# Arduino_Shield.net
KiCad netlist of a schematic drawn in EAGLE
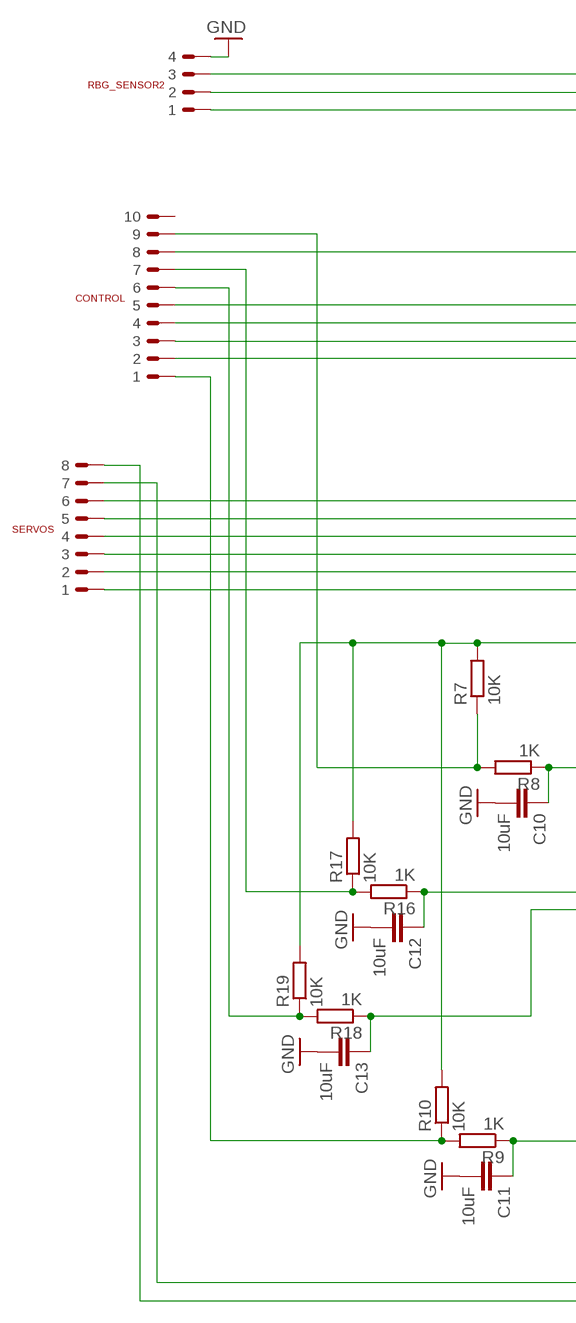
[diagram p0: schematic, sheet 1, part 1 of 2]
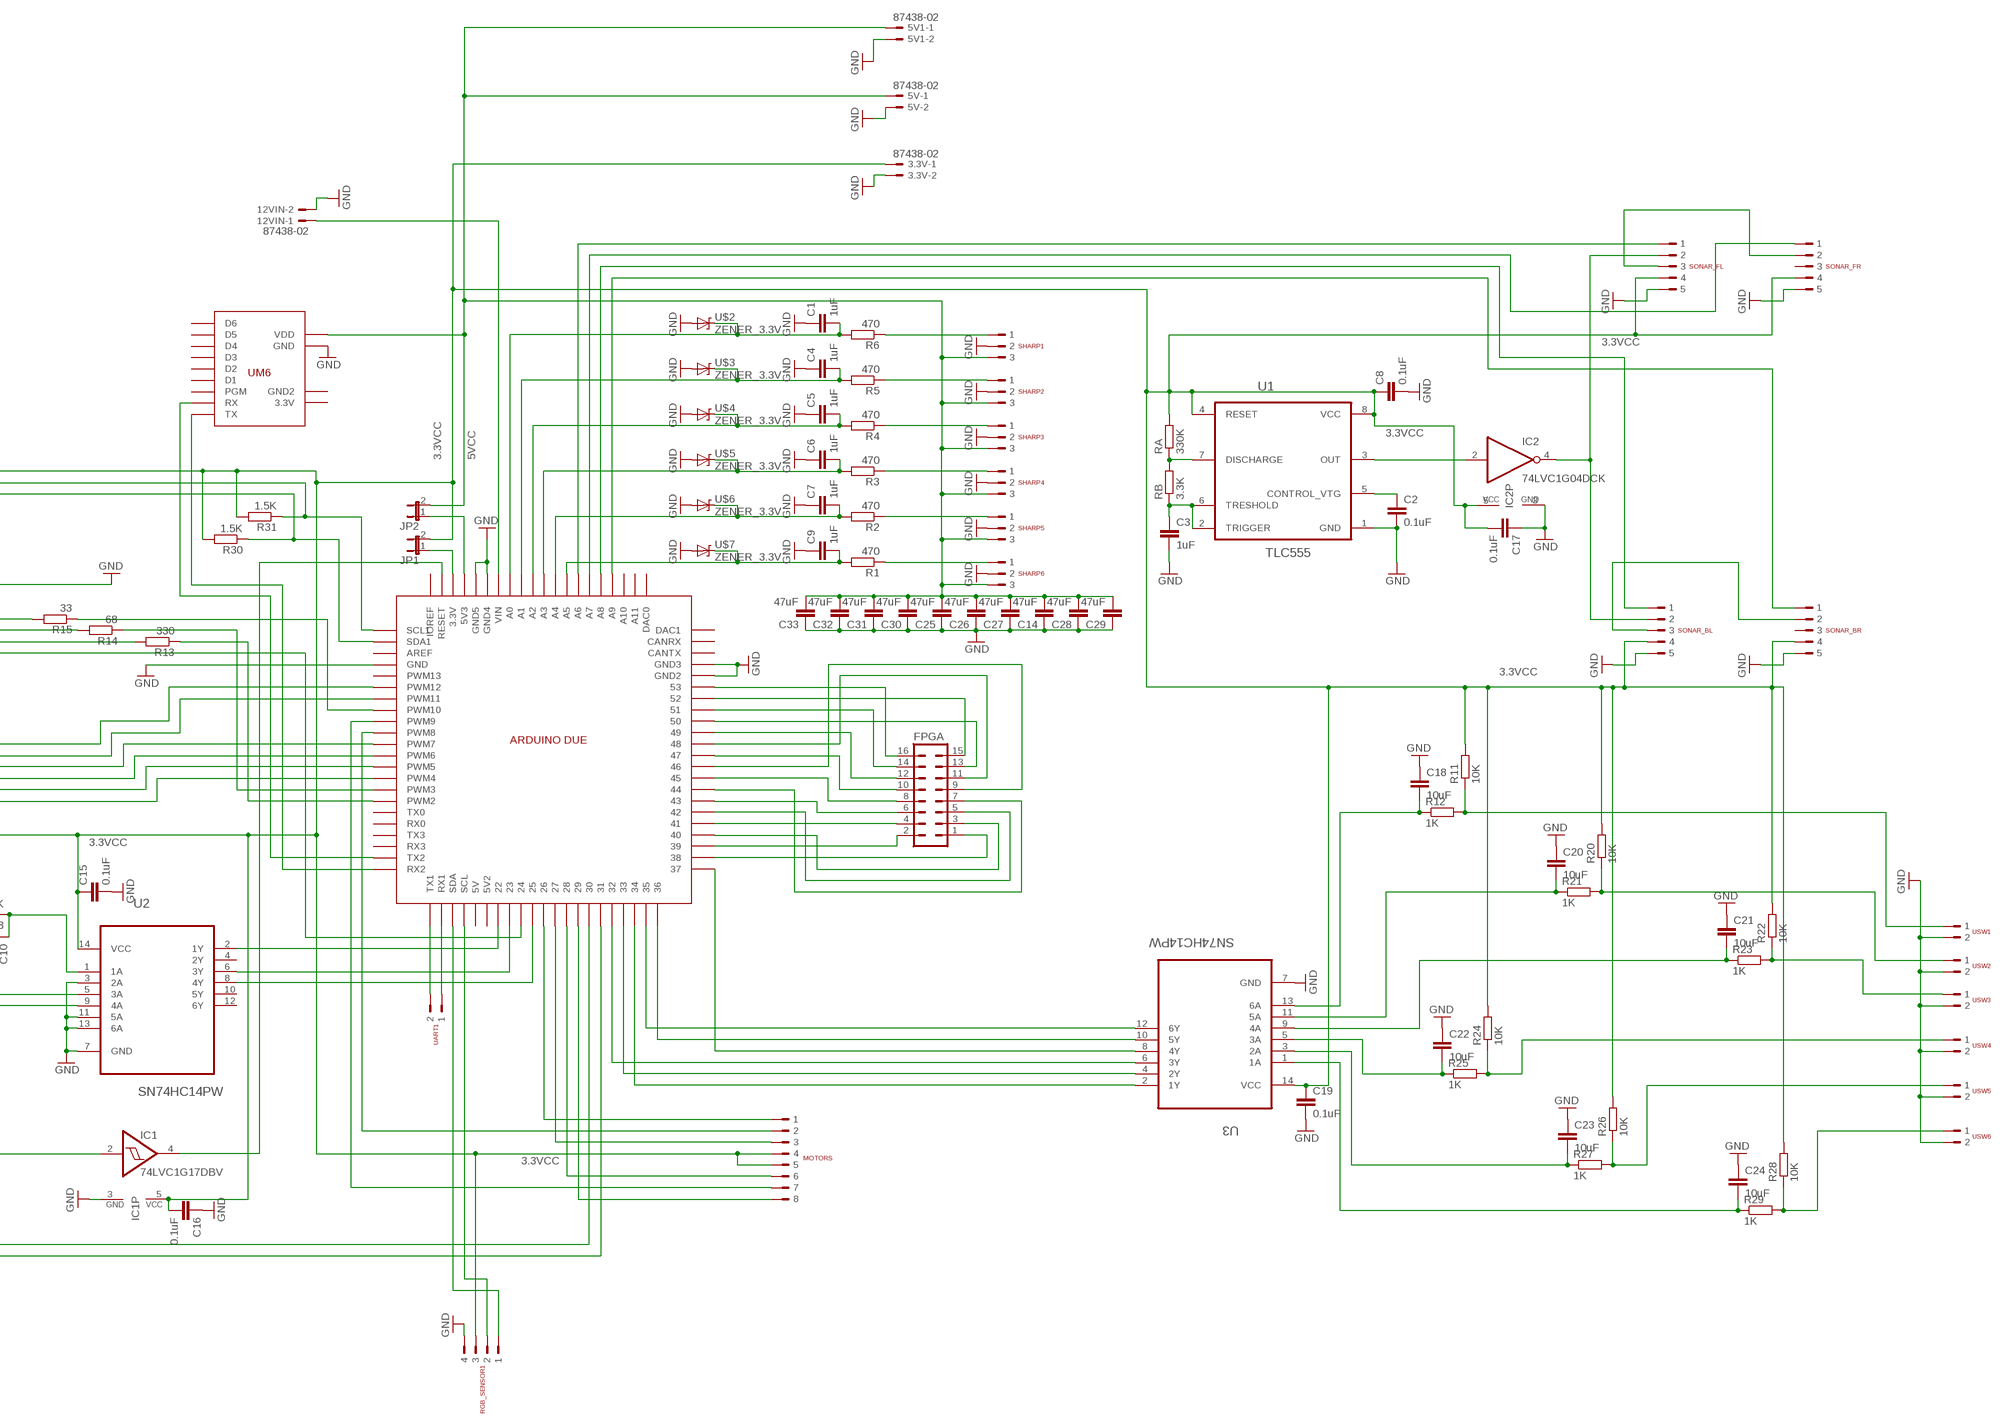
[diagram p1: schematic, sheet 1, part 2 of 2]

(export (version "E")
  (design (tool "Eeschema 10.0.6"))
  (components
    (comp (ref "3.3V")
      (value "87438-02")
      (footprint "eagle-import:87438-02")
      (libsource (lib "eagle-import") (part "87438-02"))
    )
    (comp (ref "5V")
      (value "87438-02")
      (footprint "eagle-import:87438-02")
      (libsource (lib "eagle-import") (part "87438-02"))
    )
    (comp (ref "5V1")
      (value "87438-02")
      (footprint "eagle-import:87438-02")
      (libsource (lib "eagle-import") (part "87438-02"))
    )
    (comp (ref "12VIN")
      (value "87438-02")
      (footprint "eagle-import:87438-02")
      (libsource (lib "eagle-import") (part "87438-02"))
    )
    (comp (ref "C1")
      (value "1uF")
      (footprint "eagle-import:C0603")
      (libsource (lib "eagle-import") (part "C-EUC0603"))
    )
    (comp (ref "C2")
      (value "0.1uF")
      (footprint "eagle-import:C0603")
      (libsource (lib "eagle-import") (part "C-EUC0603"))
    )
    (comp (ref "C3")
      (value "1uF")
      (footprint "eagle-import:C0603")
      (libsource (lib "eagle-import") (part "C-EUC0603"))
    )
    (comp (ref "C4")
      (value "1uF")
      (footprint "eagle-import:C0603")
      (libsource (lib "eagle-import") (part "C-EUC0603"))
    )
    (comp (ref "C5")
      (value "1uF")
      (footprint "eagle-import:C0603")
      (libsource (lib "eagle-import") (part "C-EUC0603"))
    )
    (comp (ref "C6")
      (value "1uF")
      (footprint "eagle-import:C0603")
      (libsource (lib "eagle-import") (part "C-EUC0603"))
    )
    (comp (ref "C7")
      (value "1uF")
      (footprint "eagle-import:C0603")
      (libsource (lib "eagle-import") (part "C-EUC0603"))
    )
    (comp (ref "C8")
      (value "0.1uF")
      (footprint "eagle-import:C0603")
      (libsource (lib "eagle-import") (part "C-EUC0603"))
    )
    (comp (ref "C9")
      (value "1uF")
      (footprint "eagle-import:C0603")
      (libsource (lib "eagle-import") (part "C-EUC0603"))
    )
    (comp (ref "C10")
      (value "10uF")
      (footprint "eagle-import:C0603")
      (libsource (lib "eagle-import") (part "C-EUC0603"))
    )
    (comp (ref "C11")
      (value "10uF")
      (footprint "eagle-import:C0603")
      (libsource (lib "eagle-import") (part "C-EUC0603"))
    )
    (comp (ref "C12")
      (value "10uF")
      (footprint "eagle-import:C0603")
      (libsource (lib "eagle-import") (part "C-EUC0603"))
    )
    (comp (ref "C13")
      (value "10uF")
      (footprint "eagle-import:C0603")
      (libsource (lib "eagle-import") (part "C-EUC0603"))
    )
    (comp (ref "C14")
      (value "47uF")
      (footprint "eagle-import:C1206")
      (libsource (lib "eagle-import") (part "C-EUC1206"))
    )
    (comp (ref "C15")
      (value "0.1uF")
      (footprint "eagle-import:C0603")
      (libsource (lib "eagle-import") (part "C-EUC0603"))
    )
    (comp (ref "C16")
      (value "0.1uF")
      (footprint "eagle-import:C0603")
      (libsource (lib "eagle-import") (part "C-EUC0603"))
    )
    (comp (ref "C17")
      (value "0.1uF")
      (footprint "eagle-import:C0603")
      (libsource (lib "eagle-import") (part "C-EUC0603"))
    )
    (comp (ref "C18")
      (value "10uF")
      (footprint "eagle-import:C0603")
      (libsource (lib "eagle-import") (part "C-EUC0603"))
    )
    (comp (ref "C19")
      (value "0.1uF")
      (footprint "eagle-import:C0603")
      (libsource (lib "eagle-import") (part "C-EUC0603"))
    )
    (comp (ref "C20")
      (value "10uF")
      (footprint "eagle-import:C0603")
      (libsource (lib "eagle-import") (part "C-EUC0603"))
    )
    (comp (ref "C21")
      (value "10uF")
      (footprint "eagle-import:C0603")
      (libsource (lib "eagle-import") (part "C-EUC0603"))
    )
    (comp (ref "C22")
      (value "10uF")
      (footprint "eagle-import:C0603")
      (libsource (lib "eagle-import") (part "C-EUC0603"))
    )
    (comp (ref "C23")
      (value "10uF")
      (footprint "eagle-import:C0603")
      (libsource (lib "eagle-import") (part "C-EUC0603"))
    )
    (comp (ref "C24")
      (value "10uF")
      (footprint "eagle-import:C0603")
      (libsource (lib "eagle-import") (part "C-EUC0603"))
    )
    (comp (ref "C25")
      (value "47uF")
      (footprint "eagle-import:C1206")
      (libsource (lib "eagle-import") (part "C-EUC1206"))
    )
    (comp (ref "C26")
      (value "47uF")
      (footprint "eagle-import:C1206")
      (libsource (lib "eagle-import") (part "C-EUC1206"))
    )
    (comp (ref "C27")
      (value "47uF")
      (footprint "eagle-import:C1206")
      (libsource (lib "eagle-import") (part "C-EUC1206"))
    )
    (comp (ref "C28")
      (value "47uF")
      (footprint "eagle-import:C1206")
      (libsource (lib "eagle-import") (part "C-EUC1206"))
    )
    (comp (ref "C29")
      (value "47uF")
      (footprint "eagle-import:C1206")
      (libsource (lib "eagle-import") (part "C-EUC1206"))
    )
    (comp (ref "C30")
      (value "47uF")
      (footprint "eagle-import:C1206")
      (libsource (lib "eagle-import") (part "C-EUC1206"))
    )
    (comp (ref "C31")
      (value "47uF")
      (footprint "eagle-import:C1206")
      (libsource (lib "eagle-import") (part "C-EUC1206"))
    )
    (comp (ref "C32")
      (value "47uF")
      (footprint "eagle-import:C1206")
      (libsource (lib "eagle-import") (part "C-EUC1206"))
    )
    (comp (ref "C33")
      (value "47uF")
      (footprint "eagle-import:C1206")
      (libsource (lib "eagle-import") (part "C-EUC1206"))
    )
    (comp (ref "CONTROL")
      (value "87437-1043")
      (footprint "eagle-import:87437-1043")
      (libsource (lib "eagle-import") (part "87437-1043"))
    )
    (comp (ref "FPGA")
      (value "ML16")
      (footprint "eagle-import:ML16")
      (libsource (lib "eagle-import") (part "ML16"))
    )
    (comp (ref "IC1")
      (value "74LVC1G17DBV")
      (footprint "eagle-import:SOT23-5")
      (libsource (lib "eagle-import") (part "741G17DBVLVC"))
    )
    (comp (ref "IC2")
      (value "74LVC1G04DCK")
      (footprint "eagle-import:SC70-5")
      (libsource (lib "eagle-import") (part "741G04DCKLVC"))
    )
    (comp (ref "JP1")
      (value "JP1E")
      (footprint "eagle-import:JP1")
      (libsource (lib "eagle-import") (part "JP1E"))
    )
    (comp (ref "JP2")
      (value "JP1E")
      (footprint "eagle-import:JP1")
      (libsource (lib "eagle-import") (part "JP1E"))
    )
    (comp (ref "MOTORS")
      (value "87437-0843")
      (footprint "eagle-import:87437-0843")
      (libsource (lib "eagle-import") (part "87437-0843"))
    )
    (comp (ref "R1")
      (value "470")
      (footprint "eagle-import:R0603")
      (libsource (lib "eagle-import") (part "R-EU_R0603"))
    )
    (comp (ref "R2")
      (value "470")
      (footprint "eagle-import:R0603")
      (libsource (lib "eagle-import") (part "R-EU_R0603"))
    )
    (comp (ref "R3")
      (value "470")
      (footprint "eagle-import:R0603")
      (libsource (lib "eagle-import") (part "R-EU_R0603"))
    )
    (comp (ref "R4")
      (value "470")
      (footprint "eagle-import:R0603")
      (libsource (lib "eagle-import") (part "R-EU_R0603"))
    )
    (comp (ref "R5")
      (value "470")
      (footprint "eagle-import:R0603")
      (libsource (lib "eagle-import") (part "R-EU_R0603"))
    )
    (comp (ref "R6")
      (value "470")
      (footprint "eagle-import:R0603")
      (libsource (lib "eagle-import") (part "R-EU_R0603"))
    )
    (comp (ref "R7")
      (value "10K")
      (footprint "eagle-import:R0603")
      (libsource (lib "eagle-import") (part "R-EU_R0603"))
    )
    (comp (ref "R8")
      (value "1K")
      (footprint "eagle-import:R0603")
      (libsource (lib "eagle-import") (part "R-EU_R0603"))
    )
    (comp (ref "R9")
      (value "1K")
      (footprint "eagle-import:R0603")
      (libsource (lib "eagle-import") (part "R-EU_R0603"))
    )
    (comp (ref "R10")
      (value "10K")
      (footprint "eagle-import:R0603")
      (libsource (lib "eagle-import") (part "R-EU_R0603"))
    )
    (comp (ref "R11")
      (value "10K")
      (footprint "eagle-import:R0603")
      (libsource (lib "eagle-import") (part "R-EU_R0603"))
    )
    (comp (ref "R12")
      (value "1K")
      (footprint "eagle-import:R0603")
      (libsource (lib "eagle-import") (part "R-EU_R0603"))
    )
    (comp (ref "R13")
      (value "330")
      (footprint "eagle-import:R0603")
      (libsource (lib "eagle-import") (part "R-EU_R0603"))
    )
    (comp (ref "R14")
      (value "68")
      (footprint "eagle-import:R0603")
      (libsource (lib "eagle-import") (part "R-EU_R0603"))
    )
    (comp (ref "R15")
      (value "33")
      (footprint "eagle-import:R0603")
      (libsource (lib "eagle-import") (part "R-EU_R0603"))
    )
    (comp (ref "R16")
      (value "1K")
      (footprint "eagle-import:R0603")
      (libsource (lib "eagle-import") (part "R-EU_R0603"))
    )
    (comp (ref "R17")
      (value "10K")
      (footprint "eagle-import:R0603")
      (libsource (lib "eagle-import") (part "R-EU_R0603"))
    )
    (comp (ref "R18")
      (value "1K")
      (footprint "eagle-import:R0603")
      (libsource (lib "eagle-import") (part "R-EU_R0603"))
    )
    (comp (ref "R19")
      (value "10K")
      (footprint "eagle-import:R0603")
      (libsource (lib "eagle-import") (part "R-EU_R0603"))
    )
    (comp (ref "R20")
      (value "10K")
      (footprint "eagle-import:R0603")
      (libsource (lib "eagle-import") (part "R-EU_R0603"))
    )
    (comp (ref "R21")
      (value "1K")
      (footprint "eagle-import:R0603")
      (libsource (lib "eagle-import") (part "R-EU_R0603"))
    )
    (comp (ref "R22")
      (value "10K")
      (footprint "eagle-import:R0603")
      (libsource (lib "eagle-import") (part "R-EU_R0603"))
    )
    (comp (ref "R23")
      (value "1K")
      (footprint "eagle-import:R0603")
      (libsource (lib "eagle-import") (part "R-EU_R0603"))
    )
    (comp (ref "R24")
      (value "10K")
      (footprint "eagle-import:R0603")
      (libsource (lib "eagle-import") (part "R-EU_R0603"))
    )
    (comp (ref "R25")
      (value "1K")
      (footprint "eagle-import:R0603")
      (libsource (lib "eagle-import") (part "R-EU_R0603"))
    )
    (comp (ref "R26")
      (value "10K")
      (footprint "eagle-import:R0603")
      (libsource (lib "eagle-import") (part "R-EU_R0603"))
    )
    (comp (ref "R27")
      (value "1K")
      (footprint "eagle-import:R0603")
      (libsource (lib "eagle-import") (part "R-EU_R0603"))
    )
    (comp (ref "R28")
      (value "10K")
      (footprint "eagle-import:R0603")
      (libsource (lib "eagle-import") (part "R-EU_R0603"))
    )
    (comp (ref "R29")
      (value "1K")
      (footprint "eagle-import:R0603")
      (libsource (lib "eagle-import") (part "R-EU_R0603"))
    )
    (comp (ref "R30")
      (value "1.5K")
      (footprint "eagle-import:R0603")
      (libsource (lib "eagle-import") (part "R-EU_R0603"))
    )
    (comp (ref "R31")
      (value "1.5K")
      (footprint "eagle-import:R0603")
      (libsource (lib "eagle-import") (part "R-EU_R0603"))
    )
    (comp (ref "RA")
      (value "330K")
      (footprint "eagle-import:R0603")
      (libsource (lib "eagle-import") (part "R-EU_R0603"))
    )
    (comp (ref "RB")
      (value "3.3K")
      (footprint "eagle-import:R0603")
      (libsource (lib "eagle-import") (part "R-EU_R0603"))
    )
    (comp (ref "RBG_SENSOR2")
      (value "87437-0443")
      (footprint "eagle-import:87437-0443")
      (libsource (lib "eagle-import") (part "87437-0443"))
    )
    (comp (ref "RGB_SENSOR1")
      (value "87437-0443")
      (footprint "eagle-import:87437-0443")
      (libsource (lib "eagle-import") (part "87437-0443"))
    )
    (comp (ref "SERVOS")
      (value "87437-0843")
      (footprint "eagle-import:87437-0843")
      (libsource (lib "eagle-import") (part "87437-0843"))
    )
    (comp (ref "SHARP1")
      (value "87437-0343")
      (footprint "eagle-import:87437-0343")
      (libsource (lib "eagle-import") (part "87437-0343"))
    )
    (comp (ref "SHARP2")
      (value "87437-0343")
      (footprint "eagle-import:87437-0343")
      (libsource (lib "eagle-import") (part "87437-0343"))
    )
    (comp (ref "SHARP3")
      (value "87437-0343")
      (footprint "eagle-import:87437-0343")
      (libsource (lib "eagle-import") (part "87437-0343"))
    )
    (comp (ref "SHARP4")
      (value "87437-0343")
      (footprint "eagle-import:87437-0343")
      (libsource (lib "eagle-import") (part "87437-0343"))
    )
    (comp (ref "SHARP5")
      (value "87437-0343")
      (footprint "eagle-import:87437-0343")
      (libsource (lib "eagle-import") (part "87437-0343"))
    )
    (comp (ref "SHARP6")
      (value "87437-0343")
      (footprint "eagle-import:87437-0343")
      (libsource (lib "eagle-import") (part "87437-0343"))
    )
    (comp (ref "SONAR_BL")
      (value "87437-0543")
      (footprint "eagle-import:87437-0543")
      (libsource (lib "eagle-import") (part "87437-0543"))
    )
    (comp (ref "SONAR_BR")
      (value "87437-0543")
      (footprint "eagle-import:87437-0543")
      (libsource (lib "eagle-import") (part "87437-0543"))
    )
    (comp (ref "SONAR_FL")
      (value "87437-0543")
      (footprint "eagle-import:87437-0543")
      (libsource (lib "eagle-import") (part "87437-0543"))
    )
    (comp (ref "SONAR_FR")
      (value "87437-0543")
      (footprint "eagle-import:87437-0543")
      (libsource (lib "eagle-import") (part "87437-0543"))
    )
    (comp (ref "U$1")
      (value "ARDUINO-DUE")
      (footprint "eagle-import:ARDUINO-DUE")
      (libsource (lib "eagle-import") (part "ARDUINO-DUE"))
    )
    (comp (ref "U$2")
      (value "ZENER_3.3V")
      (footprint "eagle-import:SOD-323")
      (libsource (lib "eagle-import") (part "DIODE-ZENER-BZT52"))
    )
    (comp (ref "U$3")
      (value "ZENER_3.3V")
      (footprint "eagle-import:SOD-323")
      (libsource (lib "eagle-import") (part "DIODE-ZENER-BZT52"))
    )
    (comp (ref "U$4")
      (value "ZENER_3.3V")
      (footprint "eagle-import:SOD-323")
      (libsource (lib "eagle-import") (part "DIODE-ZENER-BZT52"))
    )
    (comp (ref "U$5")
      (value "ZENER_3.3V")
      (footprint "eagle-import:SOD-323")
      (libsource (lib "eagle-import") (part "DIODE-ZENER-BZT52"))
    )
    (comp (ref "U$6")
      (value "ZENER_3.3V")
      (footprint "eagle-import:SOD-323")
      (libsource (lib "eagle-import") (part "DIODE-ZENER-BZT52"))
    )
    (comp (ref "U$7")
      (value "ZENER_3.3V")
      (footprint "eagle-import:SOD-323")
      (libsource (lib "eagle-import") (part "DIODE-ZENER-BZT52"))
    )
    (comp (ref "U1")
      (value "TLC555")
      (footprint "eagle-import:SOIC127P600X175-8N")
      (fields (field (name "MPN") "LM555CM"))
      (libsource (lib "eagle-import") (part "LM555CM"))
    )
    (comp (ref "U2")
      (value "SN74HC14PW")
      (footprint "eagle-import:SOP65P640X120-14N")
      (libsource (lib "eagle-import") (part "SN74HC14PW"))
    )
    (comp (ref "U3")
      (value "SN74HC14PW")
      (footprint "eagle-import:SOP65P640X120-14N")
      (libsource (lib "eagle-import") (part "SN74HC14PW"))
    )
    (comp (ref "UART1")
      (value "87437-0243")
      (footprint "eagle-import:87437-0243")
      (libsource (lib "eagle-import") (part "87437-0243"))
    )
    (comp (ref "UM6")
      (value "UM6")
      (footprint "eagle-import:UM6")
      (libsource (lib "eagle-import") (part "UM6"))
    )
    (comp (ref "USW1")
      (value "87437-0243")
      (footprint "eagle-import:87437-0243")
      (libsource (lib "eagle-import") (part "87437-0243"))
    )
    (comp (ref "USW2")
      (value "87437-0243")
      (footprint "eagle-import:87437-0243")
      (libsource (lib "eagle-import") (part "87437-0243"))
    )
    (comp (ref "USW3")
      (value "87437-0243")
      (footprint "eagle-import:87437-0243")
      (libsource (lib "eagle-import") (part "87437-0243"))
    )
    (comp (ref "USW4")
      (value "87437-0243")
      (footprint "eagle-import:87437-0243")
      (libsource (lib "eagle-import") (part "87437-0243"))
    )
    (comp (ref "USW5")
      (value "87437-0243")
      (footprint "eagle-import:87437-0243")
      (libsource (lib "eagle-import") (part "87437-0243"))
    )
    (comp (ref "USW6")
      (value "87437-0243")
      (footprint "eagle-import:87437-0243")
      (libsource (lib "eagle-import") (part "87437-0243"))
    )
  )
  (nets
    (net (code "1") (name "/3.3VCC") (class "Default")
      (node (ref "3.3V") (pin "1") (pinfunction "S_1") (pintype "passive"))
      (node (ref "C15") (pin "1") (pinfunction "1_1") (pintype "passive"))
      (node (ref "C16") (pin "2") (pinfunction "2_2") (pintype "passive"))
      (node (ref "C17") (pin "2") (pinfunction "2_2") (pintype "passive"))
      (node (ref "C19") (pin "1") (pinfunction "1_1") (pintype "passive"))
      (node (ref "C8") (pin "1") (pinfunction "1_1") (pintype "passive"))
      (node (ref "IC1") (pin "5") (pinfunction "VCC_5") (pintype "power_in"))
      (node (ref "IC2") (pin "5") (pinfunction "VCC_5") (pintype "power_in"))
      (node (ref "JP1") (pin "2") (pinfunction "2_2") (pintype "passive"))
      (node (ref "MOTORS") (pin "P$4") (pinfunction "4_P$4") (pintype "bidirectional"))
      (node (ref "MOTORS") (pin "P$5") (pinfunction "5_P$5") (pintype "bidirectional"))
      (node (ref "R10") (pin "2") (pinfunction "2_2") (pintype "passive"))
      (node (ref "R11") (pin "2") (pinfunction "2_2") (pintype "passive"))
      (node (ref "R17") (pin "2") (pinfunction "2_2") (pintype "passive"))
      (node (ref "R19") (pin "2") (pinfunction "2_2") (pintype "passive"))
      (node (ref "R20") (pin "2") (pinfunction "2_2") (pintype "passive"))
      (node (ref "R22") (pin "2") (pinfunction "2_2") (pintype "passive"))
      (node (ref "R24") (pin "2") (pinfunction "2_2") (pintype "passive"))
      (node (ref "R26") (pin "2") (pinfunction "2_2") (pintype "passive"))
      (node (ref "R28") (pin "2") (pinfunction "2_2") (pintype "passive"))
      (node (ref "R30") (pin "2") (pinfunction "2_2") (pintype "passive"))
      (node (ref "R31") (pin "2") (pinfunction "2_2") (pintype "passive"))
      (node (ref "R7") (pin "2") (pinfunction "2_2") (pintype "passive"))
      (node (ref "RA") (pin "2") (pinfunction "2_2") (pintype "passive"))
      (node (ref "RBG_SENSOR2") (pin "P$3") (pinfunction "3_P$3") (pintype "bidirectional"))
      (node (ref "RGB_SENSOR1") (pin "P$3") (pinfunction "3_P$3") (pintype "bidirectional"))
      (node (ref "SONAR_BL") (pin "P$4") (pinfunction "4_P$4") (pintype "bidirectional"))
      (node (ref "SONAR_BR") (pin "P$4") (pinfunction "4_P$4") (pintype "bidirectional"))
      (node (ref "SONAR_FL") (pin "P$4") (pinfunction "4_P$4") (pintype "bidirectional"))
      (node (ref "SONAR_FR") (pin "P$4") (pinfunction "4_P$4") (pintype "bidirectional"))
      (node (ref "U1") (pin "4") (pinfunction "RESET_4") (pintype "input"))
      (node (ref "U1") (pin "8") (pinfunction "VCC_8") (pintype "power_in"))
      (node (ref "U2") (pin "14") (pinfunction "VCC_14") (pintype "power_in"))
      (node (ref "U3") (pin "14") (pinfunction "VCC_14") (pintype "power_in"))
    )
    (net (code "2") (name "/5VCC") (class "Default")
      (node (ref "5V") (pin "1") (pinfunction "S_1") (pintype "passive"))
      (node (ref "5V1") (pin "1") (pinfunction "S_1") (pintype "passive"))
      (node (ref "C14") (pin "2") (pinfunction "2_2") (pintype "passive"))
      (node (ref "C25") (pin "2") (pinfunction "2_2") (pintype "passive"))
      (node (ref "C26") (pin "2") (pinfunction "2_2") (pintype "passive"))
      (node (ref "C27") (pin "2") (pinfunction "2_2") (pintype "passive"))
      (node (ref "C28") (pin "2") (pinfunction "2_2") (pintype "passive"))
      (node (ref "C29") (pin "2") (pinfunction "2_2") (pintype "passive"))
      (node (ref "C30") (pin "2") (pinfunction "2_2") (pintype "passive"))
      (node (ref "C31") (pin "2") (pinfunction "2_2") (pintype "passive"))
      (node (ref "C32") (pin "2") (pinfunction "2_2") (pintype "passive"))
      (node (ref "C33") (pin "2") (pinfunction "2_2") (pintype "passive"))
      (node (ref "JP2") (pin "2") (pinfunction "2_2") (pintype "passive"))
      (node (ref "SHARP1") (pin "P$3") (pinfunction "3_P$3") (pintype "bidirectional"))
      (node (ref "SHARP2") (pin "P$3") (pinfunction "3_P$3") (pintype "bidirectional"))
      (node (ref "SHARP3") (pin "P$3") (pinfunction "3_P$3") (pintype "bidirectional"))
      (node (ref "SHARP4") (pin "P$3") (pinfunction "3_P$3") (pintype "bidirectional"))
      (node (ref "SHARP5") (pin "P$3") (pinfunction "3_P$3") (pintype "bidirectional"))
      (node (ref "SHARP6") (pin "P$3") (pinfunction "3_P$3") (pintype "bidirectional"))
      (node (ref "UM6") (pin "P$10") (pinfunction "VDD_P$10") (pintype "bidirectional"))
    )
    (net (code "3") (name "GND") (class "Default")
      (node (ref "12VIN") (pin "2") (pinfunction "S_2") (pintype "passive"))
      (node (ref "3.3V") (pin "2") (pinfunction "S_2") (pintype "passive"))
      (node (ref "5V") (pin "2") (pinfunction "S_2") (pintype "passive"))
      (node (ref "5V1") (pin "2") (pinfunction "S_2") (pintype "passive"))
      (node (ref "C1") (pin "1") (pinfunction "1_1") (pintype "passive"))
      (node (ref "C10") (pin "2") (pinfunction "2_2") (pintype "passive"))
      (node (ref "C11") (pin "2") (pinfunction "2_2") (pintype "passive"))
      (node (ref "C12") (pin "2") (pinfunction "2_2") (pintype "passive"))
      (node (ref "C13") (pin "2") (pinfunction "2_2") (pintype "passive"))
      (node (ref "C14") (pin "1") (pinfunction "1_1") (pintype "passive"))
      (node (ref "C15") (pin "2") (pinfunction "2_2") (pintype "passive"))
      (node (ref "C16") (pin "1") (pinfunction "1_1") (pintype "passive"))
      (node (ref "C17") (pin "1") (pinfunction "1_1") (pintype "passive"))
      (node (ref "C18") (pin "1") (pinfunction "1_1") (pintype "passive"))
      (node (ref "C19") (pin "2") (pinfunction "2_2") (pintype "passive"))
      (node (ref "C2") (pin "2") (pinfunction "2_2") (pintype "passive"))
      (node (ref "C20") (pin "1") (pinfunction "1_1") (pintype "passive"))
      (node (ref "C21") (pin "1") (pinfunction "1_1") (pintype "passive"))
      (node (ref "C22") (pin "1") (pinfunction "1_1") (pintype "passive"))
      (node (ref "C23") (pin "1") (pinfunction "1_1") (pintype "passive"))
      (node (ref "C24") (pin "1") (pinfunction "1_1") (pintype "passive"))
      (node (ref "C25") (pin "1") (pinfunction "1_1") (pintype "passive"))
      (node (ref "C26") (pin "1") (pinfunction "1_1") (pintype "passive"))
      (node (ref "C27") (pin "1") (pinfunction "1_1") (pintype "passive"))
      (node (ref "C28") (pin "1") (pinfunction "1_1") (pintype "passive"))
      (node (ref "C29") (pin "1") (pinfunction "1_1") (pintype "passive"))
      (node (ref "C3") (pin "2") (pinfunction "2_2") (pintype "passive"))
      (node (ref "C30") (pin "1") (pinfunction "1_1") (pintype "passive"))
      (node (ref "C31") (pin "1") (pinfunction "1_1") (pintype "passive"))
      (node (ref "C32") (pin "1") (pinfunction "1_1") (pintype "passive"))
      (node (ref "C33") (pin "1") (pinfunction "1_1") (pintype "passive"))
      (node (ref "C4") (pin "1") (pinfunction "1_1") (pintype "passive"))
      (node (ref "C5") (pin "1") (pinfunction "1_1") (pintype "passive"))
      (node (ref "C6") (pin "1") (pinfunction "1_1") (pintype "passive"))
      (node (ref "C7") (pin "1") (pinfunction "1_1") (pintype "passive"))
      (node (ref "C8") (pin "2") (pinfunction "2_2") (pintype "passive"))
      (node (ref "C9") (pin "1") (pinfunction "1_1") (pintype "passive"))
      (node (ref "CONTROL") (pin "P$8") (pinfunction "8_P$8") (pintype "bidirectional"))
      (node (ref "IC1") (pin "3") (pinfunction "GND_3") (pintype "power_in"))
      (node (ref "IC2") (pin "3") (pinfunction "GND_3") (pintype "power_in"))
      (node (ref "RBG_SENSOR2") (pin "P$4") (pinfunction "4_P$4") (pintype "bidirectional"))
      (node (ref "RGB_SENSOR1") (pin "P$4") (pinfunction "4_P$4") (pintype "bidirectional"))
      (node (ref "SHARP1") (pin "P$2") (pinfunction "2_P$2") (pintype "bidirectional"))
      (node (ref "SHARP2") (pin "P$2") (pinfunction "2_P$2") (pintype "bidirectional"))
      (node (ref "SHARP3") (pin "P$2") (pinfunction "2_P$2") (pintype "bidirectional"))
      (node (ref "SHARP4") (pin "P$2") (pinfunction "2_P$2") (pintype "bidirectional"))
      (node (ref "SHARP5") (pin "P$2") (pinfunction "2_P$2") (pintype "bidirectional"))
      (node (ref "SHARP6") (pin "P$2") (pinfunction "2_P$2") (pintype "bidirectional"))
      (node (ref "SONAR_BL") (pin "P$5") (pinfunction "5_P$5") (pintype "bidirectional"))
      (node (ref "SONAR_BR") (pin "P$5") (pinfunction "5_P$5") (pintype "bidirectional"))
      (node (ref "SONAR_FL") (pin "P$5") (pinfunction "5_P$5") (pintype "bidirectional"))
      (node (ref "SONAR_FR") (pin "P$5") (pinfunction "5_P$5") (pintype "bidirectional"))
      (node (ref "U$1") (pin "GND") (pinfunction "GND_GND") (pintype "bidirectional"))
      (node (ref "U$1") (pin "GND2") (pinfunction "GND2_GND2") (pintype "bidirectional"))
      (node (ref "U$1") (pin "GND3") (pinfunction "GND3_GND3") (pintype "bidirectional"))
      (node (ref "U$1") (pin "GND4") (pinfunction "GND4_GND4") (pintype "bidirectional"))
      (node (ref "U$1") (pin "GND5") (pinfunction "GND5_GND5") (pintype "bidirectional"))
      (node (ref "U$2") (pin "2") (pinfunction "A_2") (pintype "passive"))
      (node (ref "U$3") (pin "2") (pinfunction "A_2") (pintype "passive"))
      (node (ref "U$4") (pin "2") (pinfunction "A_2") (pintype "passive"))
      (node (ref "U$5") (pin "2") (pinfunction "A_2") (pintype "passive"))
      (node (ref "U$6") (pin "2") (pinfunction "A_2") (pintype "passive"))
      (node (ref "U$7") (pin "2") (pinfunction "A_2") (pintype "passive"))
      (node (ref "U1") (pin "1") (pinfunction "GND_1") (pintype "passive"))
      (node (ref "U2") (pin "11") (pinfunction "5A_11") (pintype "input"))
      (node (ref "U2") (pin "13") (pinfunction "6A_13") (pintype "input"))
      (node (ref "U2") (pin "3") (pinfunction "2A_3") (pintype "input"))
      (node (ref "U2") (pin "7") (pinfunction "GND_7") (pintype "passive"))
      (node (ref "U3") (pin "7") (pinfunction "GND_7") (pintype "passive"))
      (node (ref "UM6") (pin "P$11") (pinfunction "GND_P$11") (pintype "bidirectional"))
      (node (ref "USW1") (pin "P$2") (pinfunction "2_P$2") (pintype "bidirectional"))
      (node (ref "USW2") (pin "P$2") (pinfunction "2_P$2") (pintype "bidirectional"))
      (node (ref "USW3") (pin "P$2") (pinfunction "2_P$2") (pintype "bidirectional"))
      (node (ref "USW4") (pin "P$2") (pinfunction "2_P$2") (pintype "bidirectional"))
      (node (ref "USW5") (pin "P$2") (pinfunction "2_P$2") (pintype "bidirectional"))
      (node (ref "USW6") (pin "P$2") (pinfunction "2_P$2") (pintype "bidirectional"))
    )
    (net (code "4") (name "Net-(12VINA-S)") (class "Default")
      (node (ref "12VIN") (pin "1") (pinfunction "S_1") (pintype "passive"))
      (node (ref "U$1") (pin "VIN") (pinfunction "VIN_VIN") (pintype "bidirectional"))
    )
    (net (code "5") (name "Net-(CONTROL-1)") (class "Default")
      (node (ref "CONTROL") (pin "P$1") (pinfunction "1_P$1") (pintype "bidirectional"))
      (node (ref "R10") (pin "1") (pinfunction "1_1") (pintype "passive"))
      (node (ref "R9") (pin "2") (pinfunction "2_2") (pintype "passive"))
    )
    (net (code "6") (name "Net-(CONTROL-2)") (class "Default")
      (node (ref "CONTROL") (pin "P$2") (pinfunction "2_P$2") (pintype "bidirectional"))
      (node (ref "U$1") (pin "24") (pinfunction "24_24") (pintype "bidirectional"))
    )
    (net (code "7") (name "Net-(CONTROL-3)") (class "Default")
      (node (ref "CONTROL") (pin "P$3") (pinfunction "3_P$3") (pintype "bidirectional"))
      (node (ref "R13") (pin "2") (pinfunction "2_2") (pintype "passive"))
    )
    (net (code "8") (name "Net-(CONTROL-4)") (class "Default")
      (node (ref "CONTROL") (pin "P$4") (pinfunction "4_P$4") (pintype "bidirectional"))
      (node (ref "R14") (pin "2") (pinfunction "2_2") (pintype "passive"))
    )
    (net (code "9") (name "Net-(CONTROL-5)") (class "Default")
      (node (ref "CONTROL") (pin "P$5") (pinfunction "5_P$5") (pintype "bidirectional"))
      (node (ref "R15") (pin "2") (pinfunction "2_2") (pintype "passive"))
    )
    (net (code "10") (name "Net-(CONTROL-6)") (class "Default")
      (node (ref "CONTROL") (pin "P$6") (pinfunction "6_P$6") (pintype "bidirectional"))
      (node (ref "R18") (pin "2") (pinfunction "2_2") (pintype "passive"))
      (node (ref "R19") (pin "1") (pinfunction "1_1") (pintype "passive"))
    )
    (net (code "11") (name "Net-(CONTROL-7)") (class "Default")
      (node (ref "CONTROL") (pin "P$7") (pinfunction "7_P$7") (pintype "bidirectional"))
      (node (ref "R16") (pin "2") (pinfunction "2_2") (pintype "passive"))
      (node (ref "R17") (pin "1") (pinfunction "1_1") (pintype "passive"))
    )
    (net (code "12") (name "Net-(CONTROL-9)") (class "Default")
      (node (ref "CONTROL") (pin "P$9") (pinfunction "9_P$9") (pintype "bidirectional"))
      (node (ref "R7") (pin "1") (pinfunction "1_1") (pintype "passive"))
      (node (ref "R8") (pin "2") (pinfunction "2_2") (pintype "passive"))
    )
    (net (code "13") (name "Net-(FPGA-Pad1)") (class "Default")
      (node (ref "FPGA") (pin "1") (pinfunction "1_1") (pintype "passive"))
      (node (ref "U$1") (pin "38") (pinfunction "38_38") (pintype "bidirectional"))
    )
    (net (code "14") (name "Net-(FPGA-Pad2)") (class "Default")
      (node (ref "FPGA") (pin "2") (pinfunction "2_2") (pintype "passive"))
      (node (ref "U$1") (pin "39") (pinfunction "39_39") (pintype "bidirectional"))
    )
    (net (code "15") (name "Net-(FPGA-Pad3)") (class "Default")
      (node (ref "FPGA") (pin "3") (pinfunction "3_3") (pintype "passive"))
      (node (ref "U$1") (pin "40") (pinfunction "40_40") (pintype "bidirectional"))
    )
    (net (code "16") (name "Net-(FPGA-Pad4)") (class "Default")
      (node (ref "FPGA") (pin "4") (pinfunction "4_4") (pintype "passive"))
      (node (ref "U$1") (pin "41") (pinfunction "41_41") (pintype "bidirectional"))
    )
    (net (code "17") (name "Net-(FPGA-Pad5)") (class "Default")
      (node (ref "FPGA") (pin "5") (pinfunction "5_5") (pintype "passive"))
      (node (ref "U$1") (pin "42") (pinfunction "42_42") (pintype "bidirectional"))
    )
    (net (code "18") (name "Net-(FPGA-Pad6)") (class "Default")
      (node (ref "FPGA") (pin "6") (pinfunction "6_6") (pintype "passive"))
      (node (ref "U$1") (pin "43") (pinfunction "43_43") (pintype "bidirectional"))
    )
    (net (code "19") (name "Net-(FPGA-Pad7)") (class "Default")
      (node (ref "FPGA") (pin "7") (pinfunction "7_7") (pintype "passive"))
      (node (ref "U$1") (pin "44") (pinfunction "44_44") (pintype "bidirectional"))
    )
    (net (code "20") (name "Net-(FPGA-Pad8)") (class "Default")
      (node (ref "FPGA") (pin "8") (pinfunction "8_8") (pintype "passive"))
      (node (ref "U$1") (pin "45") (pinfunction "45_45") (pintype "bidirectional"))
    )
    (net (code "21") (name "Net-(FPGA-Pad9)") (class "Default")
      (node (ref "FPGA") (pin "9") (pinfunction "9_9") (pintype "passive"))
      (node (ref "U$1") (pin "46") (pinfunction "46_46") (pintype "bidirectional"))
    )
    (net (code "22") (name "Net-(FPGA-Pad10)") (class "Default")
      (node (ref "FPGA") (pin "10") (pinfunction "10_10") (pintype "passive"))
      (node (ref "U$1") (pin "47") (pinfunction "47_47") (pintype "bidirectional"))
    )
    (net (code "23") (name "Net-(FPGA-Pad11)") (class "Default")
      (node (ref "FPGA") (pin "11") (pinfunction "11_11") (pintype "passive"))
      (node (ref "U$1") (pin "48") (pinfunction "48_48") (pintype "bidirectional"))
    )
    (net (code "24") (name "Net-(FPGA-Pad12)") (class "Default")
      (node (ref "FPGA") (pin "12") (pinfunction "12_12") (pintype "passive"))
      (node (ref "U$1") (pin "49") (pinfunction "49_49") (pintype "bidirectional"))
    )
    (net (code "25") (name "Net-(FPGA-Pad13)") (class "Default")
      (node (ref "FPGA") (pin "13") (pinfunction "13_13") (pintype "passive"))
      (node (ref "U$1") (pin "50") (pinfunction "50_50") (pintype "bidirectional"))
    )
    (net (code "26") (name "Net-(FPGA-Pad14)") (class "Default")
      (node (ref "FPGA") (pin "14") (pinfunction "14_14") (pintype "passive"))
      (node (ref "U$1") (pin "51") (pinfunction "51_51") (pintype "bidirectional"))
    )
    (net (code "27") (name "Net-(FPGA-Pad15)") (class "Default")
      (node (ref "FPGA") (pin "15") (pinfunction "15_15") (pintype "passive"))
      (node (ref "U$1") (pin "52") (pinfunction "52_52") (pintype "bidirectional"))
    )
    (net (code "28") (name "Net-(FPGA-Pad16)") (class "Default")
      (node (ref "FPGA") (pin "16") (pinfunction "16_16") (pintype "passive"))
      (node (ref "U$1") (pin "53") (pinfunction "53_53") (pintype "bidirectional"))
    )
    (net (code "29") (name "Net-(IC1A-I)") (class "Default")
      (node (ref "C11") (pin "1") (pinfunction "1_1") (pintype "passive"))
      (node (ref "IC1") (pin "2") (pinfunction "I_2") (pintype "input"))
      (node (ref "R9") (pin "1") (pinfunction "1_1") (pintype "passive"))
    )
    (net (code "30") (name "Net-(IC1A-O)") (class "Default")
      (node (ref "IC1") (pin "4") (pinfunction "O_4") (pintype "output"))
      (node (ref "U$1") (pin "RESET") (pinfunction "RESET_RESET") (pintype "bidirectional"))
    )
    (net (code "31") (name "Net-(IC2A-I)") (class "Default")
      (node (ref "IC2") (pin "2") (pinfunction "I_2") (pintype "input"))
      (node (ref "U1") (pin "3") (pinfunction "OUT_3") (pintype "output"))
    )
    (net (code "32") (name "Net-(IC2A-O)") (class "Default")
      (node (ref "IC2") (pin "4") (pinfunction "O_4") (pintype "output"))
      (node (ref "SONAR_BL") (pin "P$2") (pinfunction "2_P$2") (pintype "bidirectional"))
      (node (ref "SONAR_FL") (pin "P$2") (pinfunction "2_P$2") (pintype "bidirectional"))
    )
    (net (code "33") (name "Net-(JP1-Pad1)") (class "Default")
      (node (ref "JP1") (pin "1") (pinfunction "1_1") (pintype "passive"))
      (node (ref "U$1") (pin "3.3V") (pinfunction "3.3V_3.3V") (pintype "bidirectional"))
    )
    (net (code "34") (name "Net-(JP2-Pad1)") (class "Default")
      (node (ref "JP2") (pin "1") (pinfunction "1_1") (pintype "passive"))
      (node (ref "U$1") (pin "5V3") (pinfunction "5V3_5V3") (pintype "bidirectional"))
    )
    (net (code "35") (name "Net-(MOTORS-1)") (class "Default")
      (node (ref "MOTORS") (pin "P$1") (pinfunction "1_P$1") (pintype "bidirectional"))
      (node (ref "U$1") (pin "26") (pinfunction "26_26") (pintype "bidirectional"))
    )
    (net (code "36") (name "Net-(MOTORS-2)") (class "Default")
      (node (ref "MOTORS") (pin "P$2") (pinfunction "2_P$2") (pintype "bidirectional"))
      (node (ref "U$1") (pin "PWM8") (pinfunction "PWM8_PWM8") (pintype "bidirectional"))
    )
    (net (code "37") (name "Net-(MOTORS-3)") (class "Default")
      (node (ref "MOTORS") (pin "P$3") (pinfunction "3_P$3") (pintype "bidirectional"))
      (node (ref "U$1") (pin "27") (pinfunction "27_27") (pintype "bidirectional"))
    )
    (net (code "38") (name "Net-(MOTORS-6)") (class "Default")
      (node (ref "MOTORS") (pin "P$6") (pinfunction "6_P$6") (pintype "bidirectional"))
      (node (ref "U$1") (pin "28") (pinfunction "28_28") (pintype "bidirectional"))
    )
    (net (code "39") (name "Net-(MOTORS-7)") (class "Default")
      (node (ref "MOTORS") (pin "P$7") (pinfunction "7_P$7") (pintype "bidirectional"))
      (node (ref "U$1") (pin "PWM9") (pinfunction "PWM9_PWM9") (pintype "bidirectional"))
    )
    (net (code "40") (name "Net-(MOTORS-8)") (class "Default")
      (node (ref "MOTORS") (pin "P$8") (pinfunction "8_P$8") (pintype "bidirectional"))
      (node (ref "U$1") (pin "29") (pinfunction "29_29") (pintype "bidirectional"))
    )
    (net (code "41") (name "Net-(R13-Pad1)") (class "Default")
      (node (ref "R13") (pin "1") (pinfunction "1_1") (pintype "passive"))
      (node (ref "U$1") (pin "PWM2") (pinfunction "PWM2_PWM2") (pintype "bidirectional"))
    )
    (net (code "42") (name "Net-(R14-Pad1)") (class "Default")
      (node (ref "R14") (pin "1") (pinfunction "1_1") (pintype "passive"))
      (node (ref "U$1") (pin "PWM3") (pinfunction "PWM3_PWM3") (pintype "bidirectional"))
    )
    (net (code "43") (name "Net-(R15-Pad1)") (class "Default")
      (node (ref "R15") (pin "1") (pinfunction "1_1") (pintype "passive"))
      (node (ref "U$1") (pin "PWM10") (pinfunction "PWM10_PWM10") (pintype "bidirectional"))
    )
    (net (code "44") (name "Net-(RBG_SENSOR2-1)") (class "Default")
      (node (ref "R30") (pin "1") (pinfunction "1_1") (pintype "passive"))
      (node (ref "RBG_SENSOR2") (pin "P$1") (pinfunction "1_P$1") (pintype "bidirectional"))
      (node (ref "U$1") (pin "SDA1") (pinfunction "SDA1_SDA1") (pintype "bidirectional"))
    )
    (net (code "45") (name "Net-(RBG_SENSOR2-2)") (class "Default")
      (node (ref "R31") (pin "1") (pinfunction "1_1") (pintype "passive"))
      (node (ref "RBG_SENSOR2") (pin "P$2") (pinfunction "2_P$2") (pintype "bidirectional"))
      (node (ref "U$1") (pin "SCL1") (pinfunction "SCL1_SCL1") (pintype "bidirectional"))
    )
    (net (code "46") (name "Net-(RGB_SENSOR1-1)") (class "Default")
      (node (ref "RGB_SENSOR1") (pin "P$1") (pinfunction "1_P$1") (pintype "bidirectional"))
      (node (ref "U$1") (pin "SDA") (pinfunction "SDA_SDA") (pintype "bidirectional"))
    )
    (net (code "47") (name "Net-(RGB_SENSOR1-2)") (class "Default")
      (node (ref "RGB_SENSOR1") (pin "P$2") (pinfunction "2_P$2") (pintype "bidirectional"))
      (node (ref "U$1") (pin "SCL") (pinfunction "SCL_SCL") (pintype "bidirectional"))
    )
    (net (code "48") (name "Net-(SERVOS-1)") (class "Default")
      (node (ref "SERVOS") (pin "P$1") (pinfunction "1_P$1") (pintype "bidirectional"))
      (node (ref "U$1") (pin "PWM4") (pinfunction "PWM4_PWM4") (pintype "bidirectional"))
    )
    (net (code "49") (name "Net-(SERVOS-2)") (class "Default")
      (node (ref "SERVOS") (pin "P$2") (pinfunction "2_P$2") (pintype "bidirectional"))
      (node (ref "U$1") (pin "PWM5") (pinfunction "PWM5_PWM5") (pintype "bidirectional"))
    )
    (net (code "50") (name "Net-(SERVOS-3)") (class "Default")
      (node (ref "SERVOS") (pin "P$3") (pinfunction "3_P$3") (pintype "bidirectional"))
      (node (ref "U$1") (pin "PWM6") (pinfunction "PWM6_PWM6") (pintype "bidirectional"))
    )
    (net (code "51") (name "Net-(SERVOS-4)") (class "Default")
      (node (ref "SERVOS") (pin "P$4") (pinfunction "4_P$4") (pintype "bidirectional"))
      (node (ref "U$1") (pin "PWM7") (pinfunction "PWM7_PWM7") (pintype "bidirectional"))
    )
    (net (code "52") (name "Net-(SERVOS-5)") (class "Default")
      (node (ref "SERVOS") (pin "P$5") (pinfunction "5_P$5") (pintype "bidirectional"))
      (node (ref "U$1") (pin "PWM11") (pinfunction "PWM11_PWM11") (pintype "bidirectional"))
    )
    (net (code "53") (name "Net-(SERVOS-6)") (class "Default")
      (node (ref "SERVOS") (pin "P$6") (pinfunction "6_P$6") (pintype "bidirectional"))
      (node (ref "U$1") (pin "PWM12") (pinfunction "PWM12_PWM12") (pintype "bidirectional"))
    )
    (net (code "54") (name "Net-(SERVOS-7)") (class "Default")
      (node (ref "SERVOS") (pin "P$7") (pinfunction "7_P$7") (pintype "bidirectional"))
      (node (ref "U$1") (pin "30") (pinfunction "30_30") (pintype "bidirectional"))
    )
    (net (code "55") (name "Net-(SERVOS-8)") (class "Default")
      (node (ref "SERVOS") (pin "P$8") (pinfunction "8_P$8") (pintype "bidirectional"))
      (node (ref "U$1") (pin "31") (pinfunction "31_31") (pintype "bidirectional"))
    )
    (net (code "56") (name "Net-(SHARP1-1)") (class "Default")
      (node (ref "R6") (pin "1") (pinfunction "1_1") (pintype "passive"))
      (node (ref "SHARP1") (pin "P$1") (pinfunction "1_P$1") (pintype "bidirectional"))
    )
    (net (code "57") (name "Net-(SHARP2-1)") (class "Default")
      (node (ref "R5") (pin "1") (pinfunction "1_1") (pintype "passive"))
      (node (ref "SHARP2") (pin "P$1") (pinfunction "1_P$1") (pintype "bidirectional"))
    )
    (net (code "58") (name "Net-(SHARP3-1)") (class "Default")
      (node (ref "R4") (pin "1") (pinfunction "1_1") (pintype "passive"))
      (node (ref "SHARP3") (pin "P$1") (pinfunction "1_P$1") (pintype "bidirectional"))
    )
    (net (code "59") (name "Net-(SHARP4-1)") (class "Default")
      (node (ref "R3") (pin "1") (pinfunction "1_1") (pintype "passive"))
      (node (ref "SHARP4") (pin "P$1") (pinfunction "1_P$1") (pintype "bidirectional"))
    )
    (net (code "60") (name "Net-(SHARP5-1)") (class "Default")
      (node (ref "R2") (pin "1") (pinfunction "1_1") (pintype "passive"))
      (node (ref "SHARP5") (pin "P$1") (pinfunction "1_P$1") (pintype "bidirectional"))
    )
    (net (code "61") (name "Net-(SHARP6-1)") (class "Default")
      (node (ref "R1") (pin "1") (pinfunction "1_1") (pintype "passive"))
      (node (ref "SHARP6") (pin "P$1") (pinfunction "1_P$1") (pintype "bidirectional"))
    )
    (net (code "62") (name "Net-(SONAR_BL-1)") (class "Default")
      (node (ref "SONAR_BL") (pin "P$1") (pinfunction "1_P$1") (pintype "bidirectional"))
      (node (ref "U$1") (pin "A8") (pinfunction "A8_A8") (pintype "bidirectional"))
    )
    (net (code "63") (name "Net-(SONAR_BL-3)") (class "Default")
      (node (ref "SONAR_BL") (pin "P$3") (pinfunction "3_P$3") (pintype "bidirectional"))
      (node (ref "SONAR_BR") (pin "P$2") (pinfunction "2_P$2") (pintype "bidirectional"))
    )
    (net (code "64") (name "Net-(SONAR_BR-1)") (class "Default")
      (node (ref "SONAR_BR") (pin "P$1") (pinfunction "1_P$1") (pintype "bidirectional"))
      (node (ref "U$1") (pin "A9") (pinfunction "A9_A9") (pintype "bidirectional"))
    )
    (net (code "65") (name "Net-(SONAR_FL-1)") (class "Default")
      (node (ref "SONAR_FL") (pin "P$1") (pinfunction "1_P$1") (pintype "bidirectional"))
      (node (ref "U$1") (pin "A6") (pinfunction "A6_A6") (pintype "bidirectional"))
    )
    (net (code "66") (name "Net-(SONAR_FL-3)") (class "Default")
      (node (ref "SONAR_FL") (pin "P$3") (pinfunction "3_P$3") (pintype "bidirectional"))
      (node (ref "SONAR_FR") (pin "P$2") (pinfunction "2_P$2") (pintype "bidirectional"))
    )
    (net (code "67") (name "Net-(SONAR_FR-1)") (class "Default")
      (node (ref "SONAR_FR") (pin "P$1") (pinfunction "1_P$1") (pintype "bidirectional"))
      (node (ref "U$1") (pin "A7") (pinfunction "A7_A7") (pintype "bidirectional"))
    )
    (net (code "68") (name "Net-(U$2-C)") (class "Default")
      (node (ref "C1") (pin "2") (pinfunction "2_2") (pintype "passive"))
      (node (ref "R6") (pin "2") (pinfunction "2_2") (pintype "passive"))
      (node (ref "U$1") (pin "A0") (pinfunction "A0_A0") (pintype "bidirectional"))
      (node (ref "U$2") (pin "1") (pinfunction "C_1") (pintype "passive"))
    )
    (net (code "69") (name "Net-(U$3-C)") (class "Default")
      (node (ref "C4") (pin "2") (pinfunction "2_2") (pintype "passive"))
      (node (ref "R5") (pin "2") (pinfunction "2_2") (pintype "passive"))
      (node (ref "U$1") (pin "A1") (pinfunction "A1_A1") (pintype "bidirectional"))
      (node (ref "U$3") (pin "1") (pinfunction "C_1") (pintype "passive"))
    )
    (net (code "70") (name "Net-(U$4-C)") (class "Default")
      (node (ref "C5") (pin "2") (pinfunction "2_2") (pintype "passive"))
      (node (ref "R4") (pin "2") (pinfunction "2_2") (pintype "passive"))
      (node (ref "U$1") (pin "A2") (pinfunction "A2_A2") (pintype "bidirectional"))
      (node (ref "U$4") (pin "1") (pinfunction "C_1") (pintype "passive"))
    )
    (net (code "71") (name "Net-(U$5-C)") (class "Default")
      (node (ref "C6") (pin "2") (pinfunction "2_2") (pintype "passive"))
      (node (ref "R3") (pin "2") (pinfunction "2_2") (pintype "passive"))
      (node (ref "U$1") (pin "A3") (pinfunction "A3_A3") (pintype "bidirectional"))
      (node (ref "U$5") (pin "1") (pinfunction "C_1") (pintype "passive"))
    )
    (net (code "72") (name "Net-(U$6-C)") (class "Default")
      (node (ref "C7") (pin "2") (pinfunction "2_2") (pintype "passive"))
      (node (ref "R2") (pin "2") (pinfunction "2_2") (pintype "passive"))
      (node (ref "U$1") (pin "A4") (pinfunction "A4_A4") (pintype "bidirectional"))
      (node (ref "U$6") (pin "1") (pinfunction "C_1") (pintype "passive"))
    )
    (net (code "73") (name "Net-(U$7-C)") (class "Default")
      (node (ref "C9") (pin "2") (pinfunction "2_2") (pintype "passive"))
      (node (ref "R1") (pin "2") (pinfunction "2_2") (pintype "passive"))
      (node (ref "U$1") (pin "A5") (pinfunction "A5_A5") (pintype "bidirectional"))
      (node (ref "U$7") (pin "1") (pinfunction "C_1") (pintype "passive"))
    )
    (net (code "74") (name "Net-(U1-CONTROL_VTG)") (class "Default")
      (node (ref "C2") (pin "1") (pinfunction "1_1") (pintype "passive"))
      (node (ref "U1") (pin "5") (pinfunction "CONTROL_VTG_5") (pintype "input"))
    )
    (net (code "75") (name "Net-(U1-DISCHARGE)") (class "Default")
      (node (ref "RA") (pin "1") (pinfunction "1_1") (pintype "passive"))
      (node (ref "RB") (pin "2") (pinfunction "2_2") (pintype "passive"))
      (node (ref "U1") (pin "7") (pinfunction "DISCHARGE_7") (pintype "input"))
    )
    (net (code "76") (name "Net-(U1-TRESHOLD)") (class "Default")
      (node (ref "C3") (pin "1") (pinfunction "1_1") (pintype "passive"))
      (node (ref "RB") (pin "1") (pinfunction "1_1") (pintype "passive"))
      (node (ref "U1") (pin "2") (pinfunction "TRIGGER_2") (pintype "input"))
      (node (ref "U1") (pin "6") (pinfunction "TRESHOLD_6") (pintype "input"))
    )
    (net (code "77") (name "Net-(U2-1A)") (class "Default")
      (node (ref "C10") (pin "1") (pinfunction "1_1") (pintype "passive"))
      (node (ref "R8") (pin "1") (pinfunction "1_1") (pintype "passive"))
      (node (ref "U2") (pin "1") (pinfunction "1A_1") (pintype "input"))
    )
    (net (code "78") (name "Net-(U2-1Y)") (class "Default")
      (node (ref "U$1") (pin "22") (pinfunction "22_22") (pintype "bidirectional"))
      (node (ref "U2") (pin "2") (pinfunction "1Y_2") (pintype "output"))
    )
    (net (code "79") (name "Net-(U2-3A)") (class "Default")
      (node (ref "C12") (pin "1") (pinfunction "1_1") (pintype "passive"))
      (node (ref "R16") (pin "1") (pinfunction "1_1") (pintype "passive"))
      (node (ref "U2") (pin "5") (pinfunction "3A_5") (pintype "input"))
    )
    (net (code "80") (name "Net-(U2-3Y)") (class "Default")
      (node (ref "U$1") (pin "23") (pinfunction "23_23") (pintype "bidirectional"))
      (node (ref "U2") (pin "6") (pinfunction "3Y_6") (pintype "output"))
    )
    (net (code "81") (name "Net-(U2-4A)") (class "Default")
      (node (ref "C13") (pin "1") (pinfunction "1_1") (pintype "passive"))
      (node (ref "R18") (pin "1") (pinfunction "1_1") (pintype "passive"))
      (node (ref "U2") (pin "9") (pinfunction "4A_9") (pintype "input"))
    )
    (net (code "82") (name "Net-(U2-4Y)") (class "Default")
      (node (ref "U$1") (pin "25") (pinfunction "25_25") (pintype "bidirectional"))
      (node (ref "U2") (pin "8") (pinfunction "4Y_8") (pintype "output"))
    )
    (net (code "83") (name "Net-(U3-1A)") (class "Default")
      (node (ref "C24") (pin "2") (pinfunction "2_2") (pintype "passive"))
      (node (ref "R29") (pin "1") (pinfunction "1_1") (pintype "passive"))
      (node (ref "U3") (pin "1") (pinfunction "1A_1") (pintype "input"))
    )
    (net (code "84") (name "Net-(U3-1Y)") (class "Default")
      (node (ref "U$1") (pin "34") (pinfunction "34_34") (pintype "bidirectional"))
      (node (ref "U3") (pin "2") (pinfunction "1Y_2") (pintype "output"))
    )
    (net (code "85") (name "Net-(U3-2A)") (class "Default")
      (node (ref "C23") (pin "2") (pinfunction "2_2") (pintype "passive"))
      (node (ref "R27") (pin "1") (pinfunction "1_1") (pintype "passive"))
      (node (ref "U3") (pin "3") (pinfunction "2A_3") (pintype "input"))
    )
    (net (code "86") (name "Net-(U3-2Y)") (class "Default")
      (node (ref "U$1") (pin "33") (pinfunction "33_33") (pintype "bidirectional"))
      (node (ref "U3") (pin "4") (pinfunction "2Y_4") (pintype "output"))
    )
    (net (code "87") (name "Net-(U3-3A)") (class "Default")
      (node (ref "C22") (pin "2") (pinfunction "2_2") (pintype "passive"))
      (node (ref "R25") (pin "1") (pinfunction "1_1") (pintype "passive"))
      (node (ref "U3") (pin "5") (pinfunction "3A_5") (pintype "input"))
    )
    (net (code "88") (name "Net-(U3-3Y)") (class "Default")
      (node (ref "U$1") (pin "32") (pinfunction "32_32") (pintype "bidirectional"))
      (node (ref "U3") (pin "6") (pinfunction "3Y_6") (pintype "output"))
    )
    (net (code "89") (name "Net-(U3-4A)") (class "Default")
      (node (ref "C21") (pin "2") (pinfunction "2_2") (pintype "passive"))
      (node (ref "R23") (pin "1") (pinfunction "1_1") (pintype "passive"))
      (node (ref "U3") (pin "9") (pinfunction "4A_9") (pintype "input"))
    )
    (net (code "90") (name "Net-(U3-4Y)") (class "Default")
      (node (ref "U$1") (pin "37") (pinfunction "37_37") (pintype "bidirectional"))
      (node (ref "U3") (pin "8") (pinfunction "4Y_8") (pintype "output"))
    )
    (net (code "91") (name "Net-(U3-5A)") (class "Default")
      (node (ref "C20") (pin "2") (pinfunction "2_2") (pintype "passive"))
      (node (ref "R21") (pin "1") (pinfunction "1_1") (pintype "passive"))
      (node (ref "U3") (pin "11") (pinfunction "5A_11") (pintype "input"))
    )
    (net (code "92") (name "Net-(U3-5Y)") (class "Default")
      (node (ref "U$1") (pin "36") (pinfunction "36_36") (pintype "bidirectional"))
      (node (ref "U3") (pin "10") (pinfunction "5Y_10") (pintype "output"))
    )
    (net (code "93") (name "Net-(U3-6A)") (class "Default")
      (node (ref "C18") (pin "2") (pinfunction "2_2") (pintype "passive"))
      (node (ref "R12") (pin "1") (pinfunction "1_1") (pintype "passive"))
      (node (ref "U3") (pin "13") (pinfunction "6A_13") (pintype "input"))
    )
    (net (code "94") (name "Net-(U3-6Y)") (class "Default")
      (node (ref "U$1") (pin "35") (pinfunction "35_35") (pintype "bidirectional"))
      (node (ref "U3") (pin "12") (pinfunction "6Y_12") (pintype "output"))
    )
    (net (code "95") (name "Net-(UART1-1)") (class "Default")
      (node (ref "U$1") (pin "RX1") (pinfunction "RX1_RX1") (pintype "bidirectional"))
      (node (ref "UART1") (pin "P$1") (pinfunction "1_P$1") (pintype "bidirectional"))
    )
    (net (code "96") (name "Net-(UART1-2)") (class "Default")
      (node (ref "U$1") (pin "TX1") (pinfunction "TX1_TX1") (pintype "bidirectional"))
      (node (ref "UART1") (pin "P$2") (pinfunction "2_P$2") (pintype "bidirectional"))
    )
    (net (code "97") (name "Net-(UM6-RX)") (class "Default")
      (node (ref "U$1") (pin "TX2") (pinfunction "TX2_TX2") (pintype "bidirectional"))
      (node (ref "UM6") (pin "P$2") (pinfunction "RX_P$2") (pintype "bidirectional"))
    )
    (net (code "98") (name "Net-(UM6-TX)") (class "Default")
      (node (ref "U$1") (pin "RX2") (pinfunction "RX2_RX2") (pintype "bidirectional"))
      (node (ref "UM6") (pin "P$1") (pinfunction "TX_P$1") (pintype "bidirectional"))
    )
    (net (code "99") (name "Net-(USW1-1)") (class "Default")
      (node (ref "R11") (pin "1") (pinfunction "1_1") (pintype "passive"))
      (node (ref "R12") (pin "2") (pinfunction "2_2") (pintype "passive"))
      (node (ref "USW1") (pin "P$1") (pinfunction "1_P$1") (pintype "bidirectional"))
    )
    (net (code "100") (name "Net-(USW2-1)") (class "Default")
      (node (ref "R20") (pin "1") (pinfunction "1_1") (pintype "passive"))
      (node (ref "R21") (pin "2") (pinfunction "2_2") (pintype "passive"))
      (node (ref "USW2") (pin "P$1") (pinfunction "1_P$1") (pintype "bidirectional"))
    )
    (net (code "101") (name "Net-(USW3-1)") (class "Default")
      (node (ref "R22") (pin "1") (pinfunction "1_1") (pintype "passive"))
      (node (ref "R23") (pin "2") (pinfunction "2_2") (pintype "passive"))
      (node (ref "USW3") (pin "P$1") (pinfunction "1_P$1") (pintype "bidirectional"))
    )
    (net (code "102") (name "Net-(USW4-1)") (class "Default")
      (node (ref "R24") (pin "1") (pinfunction "1_1") (pintype "passive"))
      (node (ref "R25") (pin "2") (pinfunction "2_2") (pintype "passive"))
      (node (ref "USW4") (pin "P$1") (pinfunction "1_P$1") (pintype "bidirectional"))
    )
    (net (code "103") (name "Net-(USW5-1)") (class "Default")
      (node (ref "R26") (pin "1") (pinfunction "1_1") (pintype "passive"))
      (node (ref "R27") (pin "2") (pinfunction "2_2") (pintype "passive"))
      (node (ref "USW5") (pin "P$1") (pinfunction "1_P$1") (pintype "bidirectional"))
    )
    (net (code "104") (name "Net-(USW6-1)") (class "Default")
      (node (ref "R28") (pin "1") (pinfunction "1_1") (pintype "passive"))
      (node (ref "R29") (pin "2") (pinfunction "2_2") (pintype "passive"))
      (node (ref "USW6") (pin "P$1") (pinfunction "1_P$1") (pintype "bidirectional"))
    )
    (net (code "105") (name "unconnected-(CONTROL-10-PadP$10)") (class "Default")
      (node (ref "CONTROL") (pin "P$10") (pinfunction "10_P$10") (pintype "bidirectional"))
    )
    (net (code "106") (name "unconnected-(SONAR_BR-3-PadP$3)") (class "Default")
      (node (ref "SONAR_BR") (pin "P$3") (pinfunction "3_P$3") (pintype "bidirectional"))
    )
    (net (code "107") (name "unconnected-(SONAR_FR-3-PadP$3)") (class "Default")
      (node (ref "SONAR_FR") (pin "P$3") (pinfunction "3_P$3") (pintype "bidirectional"))
    )
    (net (code "108") (name "unconnected-(U$1-Pad5V)") (class "Default")
      (node (ref "U$1") (pin "5V") (pinfunction "5V_5V") (pintype "bidirectional"))
    )
    (net (code "109") (name "unconnected-(U$1-Pad5V2)") (class "Default")
      (node (ref "U$1") (pin "5V2") (pinfunction "5V2_5V2") (pintype "bidirectional"))
    )
    (net (code "110") (name "unconnected-(U$1-PadA10)") (class "Default")
      (node (ref "U$1") (pin "A10") (pinfunction "A10_A10") (pintype "bidirectional"))
    )
    (net (code "111") (name "unconnected-(U$1-PadA11)") (class "Default")
      (node (ref "U$1") (pin "A11") (pinfunction "A11_A11") (pintype "bidirectional"))
    )
    (net (code "112") (name "unconnected-(U$1-PadAREF)") (class "Default")
      (node (ref "U$1") (pin "AREF") (pinfunction "AREF_AREF") (pintype "bidirectional"))
    )
    (net (code "113") (name "unconnected-(U$1-PadCANRX)") (class "Default")
      (node (ref "U$1") (pin "CANRX") (pinfunction "CANRX_CANRX") (pintype "bidirectional"))
    )
    (net (code "114") (name "unconnected-(U$1-PadCANTX)") (class "Default")
      (node (ref "U$1") (pin "CANTX") (pinfunction "CANTX_CANTX") (pintype "bidirectional"))
    )
    (net (code "115") (name "unconnected-(U$1-PadDAC0)") (class "Default")
      (node (ref "U$1") (pin "DAC0") (pinfunction "DAC0_DAC0") (pintype "bidirectional"))
    )
    (net (code "116") (name "unconnected-(U$1-PadDAC1)") (class "Default")
      (node (ref "U$1") (pin "DAC1") (pinfunction "DAC1_DAC1") (pintype "bidirectional"))
    )
    (net (code "117") (name "unconnected-(U$1-PadIOREF)") (class "Default")
      (node (ref "U$1") (pin "IOREF") (pinfunction "IOREF_IOREF") (pintype "bidirectional"))
    )
    (net (code "118") (name "unconnected-(U$1-PadPWM13)") (class "Default")
      (node (ref "U$1") (pin "PWM13") (pinfunction "PWM13_PWM13") (pintype "bidirectional"))
    )
    (net (code "119") (name "unconnected-(U$1-PadRX0)") (class "Default")
      (node (ref "U$1") (pin "RX0") (pinfunction "RX0_RX0") (pintype "bidirectional"))
    )
    (net (code "120") (name "unconnected-(U$1-PadRX3)") (class "Default")
      (node (ref "U$1") (pin "RX3") (pinfunction "RX3_RX3") (pintype "bidirectional"))
    )
    (net (code "121") (name "unconnected-(U$1-PadTX0)") (class "Default")
      (node (ref "U$1") (pin "TX0") (pinfunction "TX0_TX0") (pintype "bidirectional"))
    )
    (net (code "122") (name "unconnected-(U$1-PadTX3)") (class "Default")
      (node (ref "U$1") (pin "TX3") (pinfunction "TX3_TX3") (pintype "bidirectional"))
    )
    (net (code "123") (name "unconnected-(U2-2Y-Pad4)") (class "Default")
      (node (ref "U2") (pin "4") (pinfunction "2Y_4") (pintype "output"))
    )
    (net (code "124") (name "unconnected-(U2-5Y-Pad10)") (class "Default")
      (node (ref "U2") (pin "10") (pinfunction "5Y_10") (pintype "output"))
    )
    (net (code "125") (name "unconnected-(U2-6Y-Pad12)") (class "Default")
      (node (ref "U2") (pin "12") (pinfunction "6Y_12") (pintype "output"))
    )
    (net (code "126") (name "unconnected-(UM6-3.3V-PadP$13)") (class "Default")
      (node (ref "UM6") (pin "P$13") (pinfunction "3.3V_P$13") (pintype "bidirectional"))
    )
    (net (code "127") (name "unconnected-(UM6-D1-PadP$4)") (class "Default")
      (node (ref "UM6") (pin "P$4") (pinfunction "D1_P$4") (pintype "bidirectional"))
    )
    (net (code "128") (name "unconnected-(UM6-D2-PadP$5)") (class "Default")
      (node (ref "UM6") (pin "P$5") (pinfunction "D2_P$5") (pintype "bidirectional"))
    )
    (net (code "129") (name "unconnected-(UM6-D3-PadP$6)") (class "Default")
      (node (ref "UM6") (pin "P$6") (pinfunction "D3_P$6") (pintype "bidirectional"))
    )
    (net (code "130") (name "unconnected-(UM6-D4-PadP$7)") (class "Default")
      (node (ref "UM6") (pin "P$7") (pinfunction "D4_P$7") (pintype "bidirectional"))
    )
    (net (code "131") (name "unconnected-(UM6-D5-PadP$8)") (class "Default")
      (node (ref "UM6") (pin "P$8") (pinfunction "D5_P$8") (pintype "bidirectional"))
    )
    (net (code "132") (name "unconnected-(UM6-D6-PadP$9)") (class "Default")
      (node (ref "UM6") (pin "P$9") (pinfunction "D6_P$9") (pintype "bidirectional"))
    )
    (net (code "133") (name "unconnected-(UM6-GND2-PadP$12)") (class "Default")
      (node (ref "UM6") (pin "P$12") (pinfunction "GND2_P$12") (pintype "bidirectional"))
    )
    (net (code "134") (name "unconnected-(UM6-PGM-PadP$3)") (class "Default")
      (node (ref "UM6") (pin "P$3") (pinfunction "PGM_P$3") (pintype "bidirectional"))
    )
  )
)
